# OpenRing_Power.net
KiCad netlist of a schematic drawn in Altium Designer
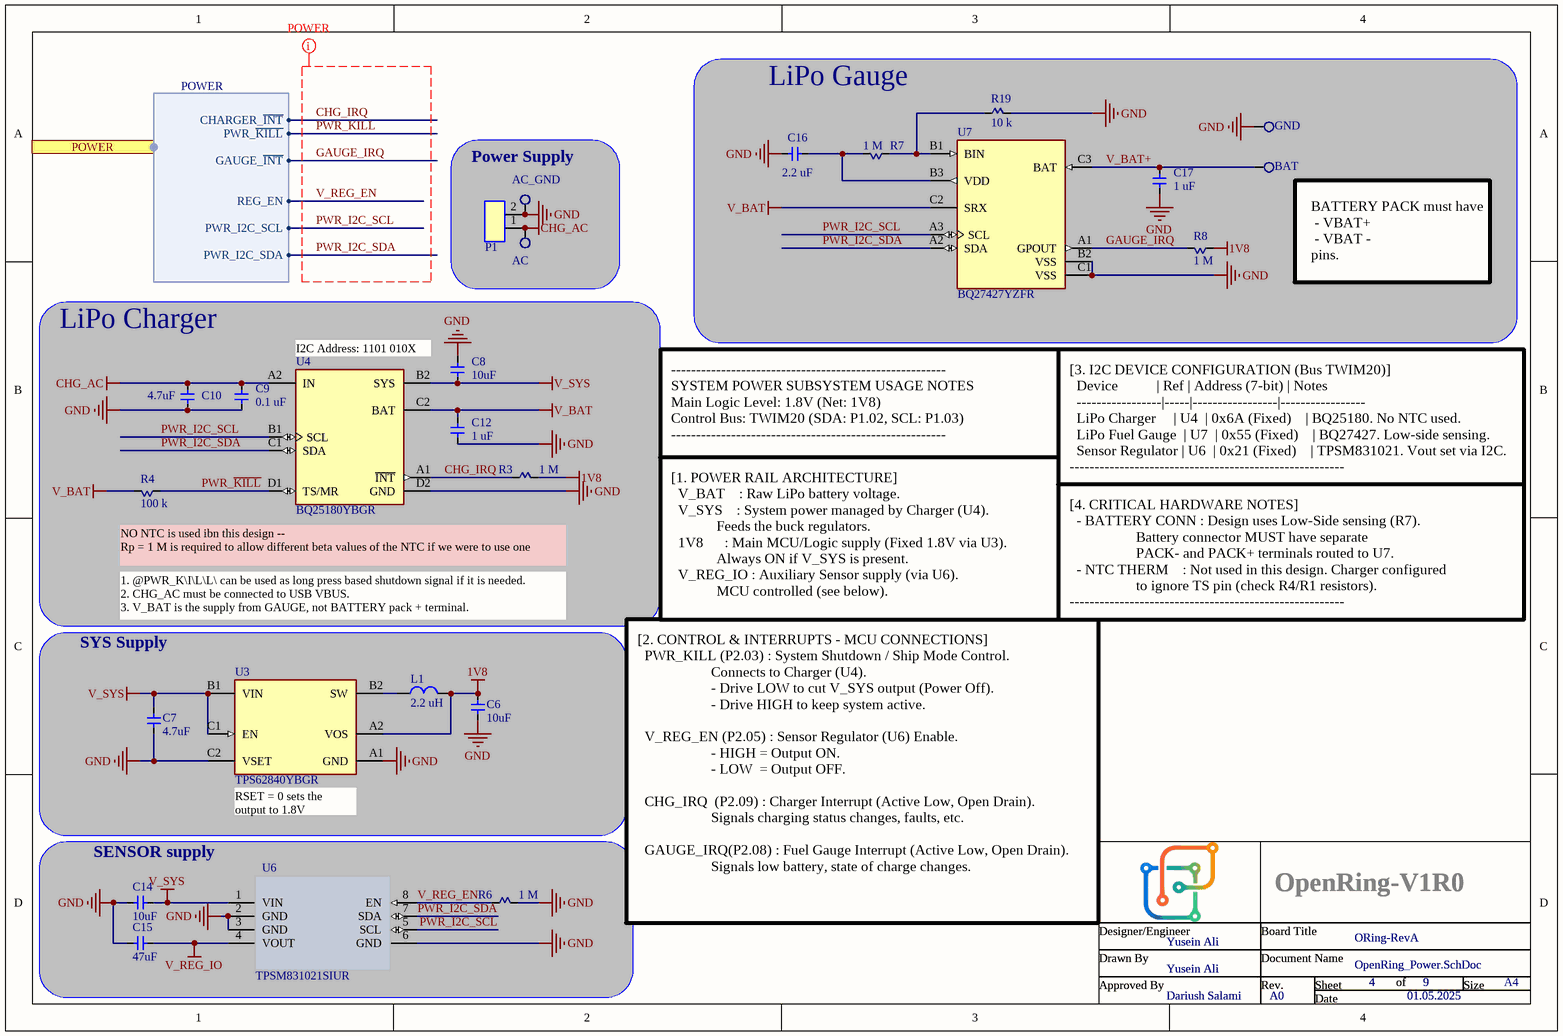
[diagram p0: OpenRing_Power.SchDoc]

(export (version "E")
  (design (tool "Eeschema 10.0.6"))
  (components
    (comp (ref "AC")
      (value "TESTPAD")
      (footprint "TEST_PAD")
      (description "TESTPOINT PIN SMD")
      (libsource (lib "OpenRingComponents") (part "TESTPAD"))
    )
    (comp (ref "AC_GND")
      (value "TESTPAD")
      (footprint "TEST_PAD")
      (description "TESTPOINT PIN SMD")
      (libsource (lib "OpenRingComponents") (part "TESTPAD"))
    )
    (comp (ref "BAT")
      (value "TESTPAD")
      (footprint "TEST_PAD")
      (description "TESTPOINT PIN SMD")
      (libsource (lib "OpenRingComponents") (part "TESTPAD"))
    )
    (comp (ref "C6")
      (value "10uF")
      (footprint "CAPC1005X05N")
      (description "Multilayer Ceramic Capacitor, 10 uF, 10 V, ± 20%, X5R, 0402 [1005 Metric]")
      (fields
        (field (name "MANUFACTURER") "Samsung")
        (field (name "MANUFACTURER PART NUMBER") "CL05A106MP5NUNC")
      )
      (libsource (lib "OpenRingComponents") (part "CL05A106MP5NUNC"))
    )
    (comp (ref "C7")
      (value "4.7uF")
      (footprint "CAPC1005X05N")
      (description "Multilayer Ceramic Capacitor, 4.7 uF, 10 V, ± 20%, X5R, 0402 [1005 Metric]")
      (fields
        (field (name "MANUFACTURER") "Murata")
        (field (name "MANUFACTURER PART NUMBER") "GRM155R61A475MEAAD")
      )
      (libsource (lib "OpenRingComponents") (part "GRM155R61A475MEAAD"))
    )
    (comp (ref "C8")
      (value "10uF")
      (footprint "CAPC1005X05N")
      (description "Multilayer Ceramic Capacitor, 10 uF, 10 V, ± 20%, X5R, 0402 [1005 Metric]")
      (fields
        (field (name "MANUFACTURER") "Samsung")
        (field (name "MANUFACTURER PART NUMBER") "CL05A106MP5NUNC")
      )
      (libsource (lib "OpenRingComponents") (part "CL05A106MP5NUNC"))
    )
    (comp (ref "C9")
      (value "0.1 uF")
      (footprint "CAPC1005X05N")
      (description "CAP CER 0.1UF 16V X5R 0402")
      (fields
        (field (name "MANUFACTURER") "Murata Electronics")
        (field (name "MANUFACTURER PART NUMBER") "GRM155R61C104KA88D")
      )
      (libsource (lib "OpenRingComponents") (part "GRM155R61C104KA88D"))
    )
    (comp (ref "C10")
      (value "4.7uF")
      (footprint "CAPC1005X05N")
      (description "Multilayer Ceramic Capacitor, 4.7 uF, 10 V, ± 20%, X5R, 0402 [1005 Metric]")
      (fields
        (field (name "MANUFACTURER") "Murata")
        (field (name "MANUFACTURER PART NUMBER") "GRM155R61A475MEAAD")
      )
      (libsource (lib "OpenRingComponents") (part "GRM155R61A475MEAAD"))
    )
    (comp (ref "C12")
      (value "1 uF")
      (footprint "CAPC1005X05N")
      (description "CAP CER 1UF 10V X5R 0402")
      (fields
        (field (name "MANUFACTURER") "Murata Electronics North America")
        (field (name "MANUFACTURER PART NUMBER") "GRM155R61A105KE15D")
      )
      (libsource (lib "OpenRingComponents") (part "GRM155R61A105KE15D"))
    )
    (comp (ref "C14")
      (value "10uF")
      (footprint "CAPC1005X05N")
      (description "Multilayer Ceramic Capacitor, 10 uF, 10 V, ± 20%, X5R, 0402 [1005 Metric]")
      (fields
        (field (name "MANUFACTURER") "Samsung")
        (field (name "MANUFACTURER PART NUMBER") "CL05A106MP5NUNC")
      )
      (libsource (lib "OpenRingComponents") (part "CL05A106MP5NUNC"))
    )
    (comp (ref "C15")
      (value "47uF")
      (footprint "CAPC1610X05N")
      (description "CL10 Series 0603 47 uF 6.3 V ±20% Tolerance X5R Multilayer Ceramic Capacitor")
      (fields
        (field (name "MANUFACTURER") "Samsung")
        (field (name "MANUFACTURER PART NUMBER") "CL10A476MQ8QRNC")
      )
      (libsource (lib "OpenRingComponents") (part "CL10A476MQ8QRNC"))
    )
    (comp (ref "C16")
      (value "2.2 uF")
      (footprint "CAPC1005X05N")
      (description "CAP CER 2.2UF 10V X5R 0402")
      (fields
        (field (name "MANUFACTURER") "Murata Electronics North America")
        (field (name "MANUFACTURER PART NUMBER") "GRM155R61A225KE95D")
      )
      (libsource (lib "OpenRingComponents") (part "GRM155R61A225KE95D"))
    )
    (comp (ref "C17")
      (value "1 uF")
      (footprint "CAPC1005X05N")
      (description "CAP CER 1UF 10V X5R 0402")
      (fields
        (field (name "MANUFACTURER") "Murata Electronics North America")
        (field (name "MANUFACTURER PART NUMBER") "GRM155R61A105KE15D")
      )
      (libsource (lib "OpenRingComponents") (part "GRM155R61A105KE15D"))
    )
    (comp (ref "GND")
      (value "TESTPAD")
      (footprint "TEST_PAD")
      (description "TESTPOINT PIN SMD")
      (libsource (lib "OpenRingComponents") (part "TESTPAD"))
    )
    (comp (ref "L1")
      (value "2.2 uH")
      (footprint "FP-DFE201612C-MFG")
      (description "Inductor Power Shielded Wirewound 2.2uH 20% 1MHz Metal 1.8A 0.116Ohm DCR 0806 T/R")
      (fields
        (field (name "MANUFACTURER") "Murata")
        (field (name "MANUFACTURER PART NUMBER") "DFE201612E-2R2M=P2")
      )
      (libsource (lib "OpenRingComponents") (part "DFE201612E-2R2M=P2"))
    )
    (comp (ref "P1")
      (value "RM-1238-B02-41")
      (footprint "RM-1238-B02-41_2")
      (description "RM-1238-B02-41 by www.xtpogopin.com")
      (fields (field (name "MANUFACTURER") "XTPogoPin"))
      (libsource (lib "Connectors") (part "RM-1238-B02-41"))
    )
    (comp (ref "R3")
      (value "1 M")
      (footprint "RESC1005X04N")
      (description "RES SMD 1M OHM 1% 1/10W 0402")
      (fields
        (field (name "MANUFACTURER") "Panasonic Electronic Components")
        (field (name "MANUFACTURER PART NUMBER") "ERJ-2RKF1004X")
      )
      (libsource (lib "OpenRingComponents") (part "ERJ-2RKF1004X"))
    )
    (comp (ref "R4")
      (value "100 k")
      (footprint "RESC1005X04N")
      (description "RES SMD 100K OHM 1% 1/10W 0402")
      (fields
        (field (name "MANUFACTURER") "Panasonic Electronic Components")
        (field (name "MANUFACTURER PART NUMBER") "ERJ-2RKF1003X")
      )
      (libsource (lib "OpenRingComponents") (part "ERJ-2RKF1003X"))
    )
    (comp (ref "R6")
      (value "1 M")
      (footprint "RESC1005X04N")
      (description "RES SMD 1M OHM 1% 1/10W 0402")
      (fields
        (field (name "MANUFACTURER") "Panasonic Electronic Components")
        (field (name "MANUFACTURER PART NUMBER") "ERJ-2RKF1004X")
      )
      (libsource (lib "OpenRingComponents") (part "ERJ-2RKF1004X"))
    )
    (comp (ref "R7")
      (value "1 M")
      (footprint "RESC1005X04N")
      (description "RES SMD 1M OHM 1% 1/10W 0402")
      (fields
        (field (name "MANUFACTURER") "Panasonic Electronic Components")
        (field (name "MANUFACTURER PART NUMBER") "ERJ-2RKF1004X")
      )
      (libsource (lib "OpenRingComponents") (part "ERJ-2RKF1004X"))
    )
    (comp (ref "R8")
      (value "1 M")
      (footprint "RESC1005X04N")
      (description "RES SMD 1M OHM 1% 1/10W 0402")
      (fields
        (field (name "MANUFACTURER") "Panasonic Electronic Components")
        (field (name "MANUFACTURER PART NUMBER") "ERJ-2RKF1004X")
      )
      (libsource (lib "OpenRingComponents") (part "ERJ-2RKF1004X"))
    )
    (comp (ref "R19")
      (value "10 k")
      (footprint "RESC1005X04N")
      (description "RES SMD 10K OHM 1% 1/10W 0402")
      (fields
        (field (name "MANUFACTURER") "Panasonic Electronic Components")
        (field (name "MANUFACTURER PART NUMBER") "ERJ-2RKF1002X")
      )
      (libsource (lib "OpenRingComponents") (part "ERJ-2RKF1002X"))
    )
    (comp (ref "U3")
      (value "TPS62840YBGR")
      (footprint "BGA6C40P2X3_97X147X50")
      (description "Conv DC-DC 1.8V to 6.5V Synchronous Step Down Single-Out 1.8V to 3.3V 0.75A 6-Pin DSBGA T/R")
      (fields (field (name "MANUFACTURER") "Texas Instruments"))
      (libsource (lib "OpenRingComponents") (part "TPS62840YBGR"))
    )
    (comp (ref "U4")
      (value "BQ25180YBGR")
      (footprint "BGA8C40P2X4_104X159X50")
      (description "1-A Li-ion I²C programmable charger with regulated power path in WCSP package 8-DSBGA -40 to 85")
      (fields (field (name "MANUFACTURER") "Texas Instruments"))
      (libsource (lib "OpenRingComponents") (part "BQ25180YBGR"))
    )
    (comp (ref "U6")
      (value "TPSM831021SIUR")
      (footprint "MicroSiP8_SIU-A_TEX-M")
      (fields (field (name "MANUFACTURER") "Texas Instruments"))
      (libsource (lib "OpenRingComponents") (part "TPSM831021SIUR"))
    )
    (comp (ref "U7")
      (value "BQ27427YZFR")
      (footprint "BGA9C50P3X3_158X162X62")
      (fields (field (name "MANUFACTURER") "Texas Instruments"))
      (libsource (lib "OpenRingComponents") (part "BQ27427YZFR"))
    )
  )
  (nets
    (net (code "2") (name "/CHG_IRQ") (class "Default")
      (node (ref "R3") (pin "2") (pinfunction "2_2") (pintype "passive"))
      (node (ref "U4") (pin "A1") (pinfunction "~{INT}_A1") (pintype "output"))
    )
    (net (code "3") (name "/GAUGE_IRQ") (class "Default")
      (node (ref "R8") (pin "2") (pinfunction "2_2") (pintype "passive"))
      (node (ref "U7") (pin "A1") (pinfunction "GPOUT_A1") (pintype "output"))
    )
    (net (code "4") (name "/PWR_I2C_SCL") (class "Default")
      (node (ref "U4") (pin "B1") (pinfunction "SCL_B1") (pintype "bidirectional"))
      (node (ref "U6") (pin "5") (pinfunction "SCL_5") (pintype "bidirectional"))
      (node (ref "U7") (pin "A3") (pinfunction "SCL_A3") (pintype "bidirectional"))
    )
    (net (code "5") (name "/PWR_I2C_SDA") (class "Default")
      (node (ref "U4") (pin "C1") (pinfunction "SDA_C1") (pintype "bidirectional"))
      (node (ref "U6") (pin "7") (pinfunction "SDA_7") (pintype "bidirectional"))
      (node (ref "U7") (pin "A2") (pinfunction "SDA_A2") (pintype "bidirectional"))
    )
    (net (code "6") (name "/PWR_~{KILL}") (class "Default")
      (node (ref "R4") (pin "1") (pinfunction "1_1") (pintype "passive"))
      (node (ref "U4") (pin "D1") (pinfunction "TS/MR_D1") (pintype "bidirectional"))
    )
    (net (code "7") (name "/V_BAT+") (class "Default")
      (node (ref "BAT") (pin "1") (pinfunction "1_1") (pintype "passive"))
      (node (ref "C17") (pin "1") (pinfunction "1_1") (pintype "passive"))
      (node (ref "U7") (pin "C3") (pinfunction "BAT_C3") (pintype "input"))
    )
    (net (code "8") (name "/V_REG_EN") (class "Default")
      (node (ref "R6") (pin "2") (pinfunction "2_2") (pintype "passive"))
      (node (ref "U6") (pin "8") (pinfunction "EN_8") (pintype "input"))
    )
    (net (code "10") (name "1V8") (class "Default")
      (node (ref "C6") (pin "1") (pinfunction "1_1") (pintype "passive"))
      (node (ref "L1") (pin "2") (pinfunction "2_2") (pintype "passive"))
      (node (ref "R3") (pin "1") (pinfunction "1_1") (pintype "passive"))
      (node (ref "R8") (pin "1") (pinfunction "1_1") (pintype "passive"))
      (node (ref "U3") (pin "A2") (pinfunction "VOS_A2") (pintype "power_in"))
    )
    (net (code "11") (name "CHG_AC") (class "Default")
      (node (ref "AC") (pin "1") (pinfunction "1_1") (pintype "passive"))
      (node (ref "C10") (pin "2") (pinfunction "2_2") (pintype "passive"))
      (node (ref "C9") (pin "1") (pinfunction "1_1") (pintype "passive"))
      (node (ref "P1") (pin "1") (pinfunction "1_1") (pintype "passive"))
      (node (ref "U4") (pin "A2") (pinfunction "IN_A2") (pintype "power_in"))
    )
    (net (code "12") (name "GND") (class "Default")
      (node (ref "AC_GND") (pin "1") (pinfunction "1_1") (pintype "passive"))
      (node (ref "C10") (pin "1") (pinfunction "1_1") (pintype "passive"))
      (node (ref "C12") (pin "2") (pinfunction "2_2") (pintype "passive"))
      (node (ref "C14") (pin "1") (pinfunction "1_1") (pintype "passive"))
      (node (ref "C15") (pin "1") (pinfunction "1_1") (pintype "passive"))
      (node (ref "C16") (pin "2") (pinfunction "2_2") (pintype "passive"))
      (node (ref "C17") (pin "2") (pinfunction "2_2") (pintype "passive"))
      (node (ref "C6") (pin "2") (pinfunction "2_2") (pintype "passive"))
      (node (ref "C7") (pin "1") (pinfunction "1_1") (pintype "passive"))
      (node (ref "C8") (pin "2") (pinfunction "2_2") (pintype "passive"))
      (node (ref "C9") (pin "2") (pinfunction "2_2") (pintype "passive"))
      (node (ref "GND") (pin "1") (pinfunction "1_1") (pintype "passive"))
      (node (ref "P1") (pin "2") (pinfunction "2_2") (pintype "passive"))
      (node (ref "R19") (pin "2") (pinfunction "2_2") (pintype "passive"))
      (node (ref "R6") (pin "1") (pinfunction "1_1") (pintype "passive"))
      (node (ref "U3") (pin "A1") (pinfunction "GND_A1") (pintype "power_in"))
      (node (ref "U3") (pin "C2") (pinfunction "VSET_C2") (pintype "power_in"))
      (node (ref "U4") (pin "D2") (pinfunction "GND_D2") (pintype "power_in"))
      (node (ref "U6") (pin "2") (pinfunction "GND_2") (pintype "power_in"))
      (node (ref "U6") (pin "3") (pinfunction "GND_3") (pintype "power_in"))
      (node (ref "U6") (pin "6") (pinfunction "GND_6") (pintype "power_in"))
      (node (ref "U7") (pin "B2") (pinfunction "VSS_B2") (pintype "power_in"))
      (node (ref "U7") (pin "C1") (pinfunction "VSS_C1") (pintype "power_in"))
    )
    (net (code "13") (name "Net-(U3-SW)") (class "Default")
      (node (ref "L1") (pin "1") (pinfunction "1_1") (pintype "passive"))
      (node (ref "U3") (pin "B2") (pinfunction "SW_B2") (pintype "power_in"))
    )
    (net (code "14") (name "Net-(U7-BIN)") (class "Default")
      (node (ref "R19") (pin "1") (pinfunction "1_1") (pintype "passive"))
      (node (ref "R7") (pin "1") (pinfunction "1_1") (pintype "passive"))
      (node (ref "U7") (pin "B1") (pinfunction "BIN_B1") (pintype "input"))
    )
    (net (code "15") (name "Net-(U7-VDD)") (class "Default")
      (node (ref "C16") (pin "1") (pinfunction "1_1") (pintype "passive"))
      (node (ref "R7") (pin "2") (pinfunction "2_2") (pintype "passive"))
      (node (ref "U7") (pin "B3") (pinfunction "VDD_B3") (pintype "output"))
    )
    (net (code "16") (name "V_BAT") (class "Default")
      (node (ref "C12") (pin "1") (pinfunction "1_1") (pintype "passive"))
      (node (ref "R4") (pin "2") (pinfunction "2_2") (pintype "passive"))
      (node (ref "U4") (pin "C2") (pinfunction "BAT_C2") (pintype "power_in"))
      (node (ref "U7") (pin "C2") (pinfunction "SRX_C2") (pintype "power_in"))
    )
    (net (code "17") (name "V_REG_IO") (class "Default")
      (node (ref "C15") (pin "2") (pinfunction "2_2") (pintype "passive"))
      (node (ref "U6") (pin "4") (pinfunction "VOUT_4") (pintype "power_in"))
    )
    (net (code "18") (name "V_SYS") (class "Default")
      (node (ref "C14") (pin "2") (pinfunction "2_2") (pintype "passive"))
      (node (ref "C7") (pin "2") (pinfunction "2_2") (pintype "passive"))
      (node (ref "C8") (pin "1") (pinfunction "1_1") (pintype "passive"))
      (node (ref "U3") (pin "B1") (pinfunction "VIN_B1") (pintype "power_in"))
      (node (ref "U3") (pin "C1") (pinfunction "EN_C1") (pintype "input"))
      (node (ref "U4") (pin "B2") (pinfunction "SYS_B2") (pintype "power_in"))
      (node (ref "U6") (pin "1") (pinfunction "VIN_1") (pintype "power_in"))
    )
  )
)
